# sensor_board.net
KiCad netlist of a schematic drawn in Altium Designer
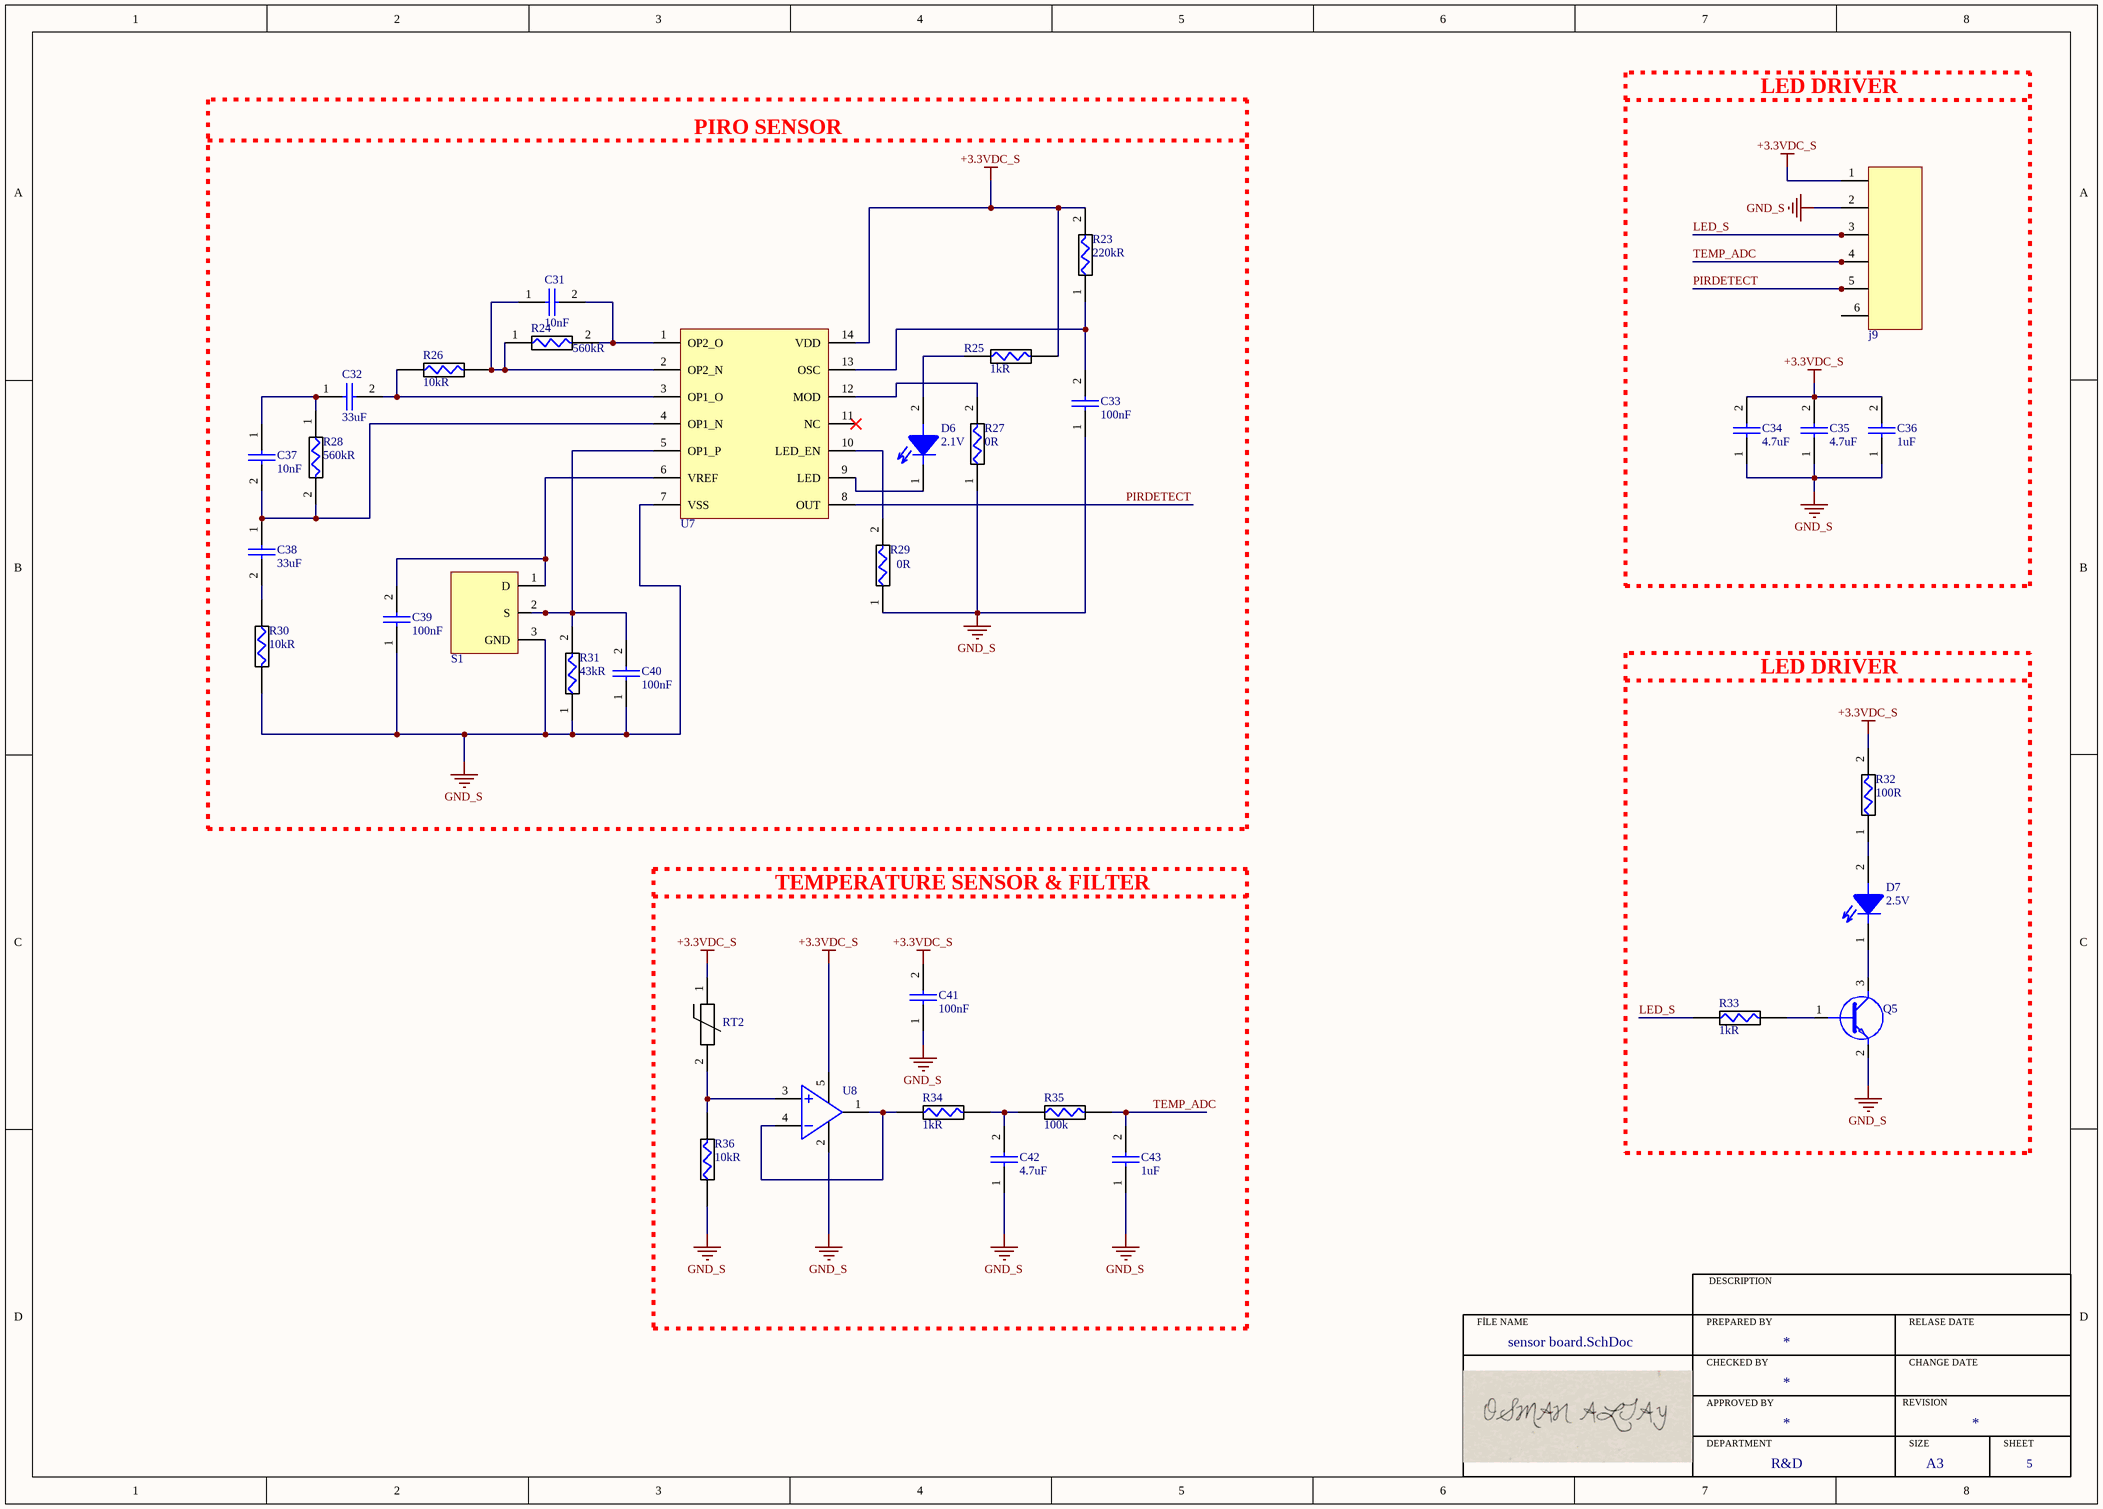
[diagram p0: sensor board.SchDoc]

(export (version "E")
  (design (tool "Eeschema 10.0.6"))
  (components
    (comp (ref "C31")
      (value "10nF")
      (footprint "CAP_0603")
      (description "CAP CER 10nF %10 0603")
      (fields
        (field (name "MANUFACTURER") "Walsin Technologies")
        (field (name "MANUFACTURER PART NUMBER") "0603B103K160CT")
        (field (name "DESIGNED BY") "Osman")
      )
      (libsource (lib "udemy_library") (part "CAP CER 10nF 0603"))
    )
    (comp (ref "C32")
      (value "33uF")
      (footprint "CAP_1206")
      (description "Multilayer Ceramic Capacitor, 33 uF, 25 V, ± 20%, X5R, 1206 [3216 Metric]")
      (fields
        (field (name "MANUFACTURER") "TDK")
        (field (name "MANUFACTURER PART NUMBER") "C3216X5R1E336M160AC")
      )
      (libsource (lib "udemy_library") (part "CAP CER 33uF 0603"))
    )
    (comp (ref "C33")
      (value "100nF")
      (footprint "CAP_0603")
      (description "Capacitor, 0.1UF, 100V, MLCC, 0603;")
      (fields
        (field (name "MANUFACTURER") "KEMET")
        (field (name "MANUFACTURER PART NUMBER") "C0603C104K1RACTU")
        (field (name "DESIGNED BY") "Osman")
      )
      (libsource (lib "udemy_library") (part "CAP CER 100nf 0603"))
    )
    (comp (ref "C34")
      (value "4.7uF")
      (footprint "CAP_0805")
      (description "CAP CER 4.7uF %10 0805")
      (fields
        (field (name "MANUFACTURER") "Samsung")
        (field (name "MANUFACTURER PART NUMBER") "CL21A475KAQNNNE")
      )
      (libsource (lib "udemy_library") (part "CAP CER 4.7uF 0805"))
    )
    (comp (ref "C35")
      (value "4.7uF")
      (footprint "CAP_0805")
      (description "CAP CER 4.7uF %10 0805")
      (fields
        (field (name "MANUFACTURER") "Samsung")
        (field (name "MANUFACTURER PART NUMBER") "CL21A475KAQNNNE")
      )
      (libsource (lib "udemy_library") (part "CAP CER 4.7uF 0805"))
    )
    (comp (ref "C36")
      (value "1uF")
      (footprint "CAP_0805")
      (description "CAP CER 1uF %10 0805")
      (fields
        (field (name "MANUFACTURER") "Samsung")
        (field (name "MANUFACTURER PART NUMBER") "CL21B105KBFNNNE")
        (field (name "DESIGNED BY") "Osman")
      )
      (libsource (lib "udemy_library") (part "CAP CER 1uF 0805"))
    )
    (comp (ref "C37")
      (value "10nF")
      (footprint "CAP_0603")
      (description "CAP CER 10nF %10 0603")
      (fields
        (field (name "MANUFACTURER") "Walsin Technologies")
        (field (name "MANUFACTURER PART NUMBER") "0603B103K160CT")
        (field (name "DESIGNED BY") "Osman")
      )
      (libsource (lib "udemy_library") (part "CAP CER 10nF 0603"))
    )
    (comp (ref "C38")
      (value "33uF")
      (footprint "CAP_1206")
      (description "Multilayer Ceramic Capacitor, 33 uF, 25 V, ± 20%, X5R, 1206 [3216 Metric]")
      (fields
        (field (name "MANUFACTURER") "TDK")
        (field (name "MANUFACTURER PART NUMBER") "C3216X5R1E336M160AC")
      )
      (libsource (lib "udemy_library") (part "CAP CER 33uF 0603"))
    )
    (comp (ref "C39")
      (value "100nF")
      (footprint "CAP_0603")
      (description "Capacitor, 0.1UF, 100V, MLCC, 0603;")
      (fields
        (field (name "MANUFACTURER") "KEMET")
        (field (name "MANUFACTURER PART NUMBER") "C0603C104K1RACTU")
        (field (name "DESIGNED BY") "Osman")
      )
      (libsource (lib "udemy_library") (part "CAP CER 100nf 0603"))
    )
    (comp (ref "C40")
      (value "100nF")
      (footprint "CAP_0603")
      (description "Capacitor, 0.1UF, 100V, MLCC, 0603;")
      (fields
        (field (name "MANUFACTURER") "KEMET")
        (field (name "MANUFACTURER PART NUMBER") "C0603C104K1RACTU")
        (field (name "DESIGNED BY") "Osman")
      )
      (libsource (lib "udemy_library") (part "CAP CER 100nf 0603"))
    )
    (comp (ref "C41")
      (value "100nF")
      (footprint "CAP_0805")
      (description "CL21B104KBCNNNC")
      (fields
        (field (name "MANUFACTURER") "Samsung")
        (field (name "TOLERANCE") "10%")
        (field (name "DESIGNED BY") "OSMAN")
      )
      (libsource (lib "udemy_library") (part "CAP CER 100nF 0805"))
    )
    (comp (ref "C42")
      (value "4.7uF")
      (footprint "CAP_0805")
      (description "CAP CER 4.7uF %10 0805")
      (fields
        (field (name "MANUFACTURER") "Samsung")
        (field (name "MANUFACTURER PART NUMBER") "CL21A475KAQNNNE")
      )
      (libsource (lib "udemy_library") (part "CAP CER 4.7uF 0805"))
    )
    (comp (ref "C43")
      (value "1uF")
      (footprint "CAP_0805")
      (description "CAP CER 1uF %10 0805")
      (fields
        (field (name "MANUFACTURER") "Samsung")
        (field (name "MANUFACTURER PART NUMBER") "CL21B105KBFNNNE")
        (field (name "DESIGNED BY") "Osman")
      )
      (libsource (lib "udemy_library") (part "CAP CER 1uF 0805"))
    )
    (comp (ref "D6")
      (value "CMD17-21VGD/TR8")
      (footprint "LED_GREEN_0805")
      (description "CML CMD17-21VGD/TR8 LED SMT 0805 2.1V 7mcd 140deg Green 3K Part of the VCC Family of Products")
      (fields (field (name "MANUFACTURER") "VCC CHML") (field (name "FOWARD VOLTAGE") "2.1V"))
      (libsource (lib "udemy_library") (part "LED GREEN 0805"))
    )
    (comp (ref "D7")
      (value "LS R976-NR-1")
      (footprint "LED_RED_0805")
      (description "LED Uni-Color Super Red 645nm 2-Pin Chip 0805(2012Metric) T/R")
      (fields
        (field (name "MANUFACTURER") "Osram Opto")
        (field (name "MANUFACTURER PART NUMBER") "LSR976-NR-1")
        (field (name "FORWARD VOLTAGE") "2.5V")
        (field (name "DESIGNED BY") "Osman")
      )
      (libsource (lib "udemy_library") (part "LED RED 0805"))
    )
    (comp (ref "j9")
      (value "64800611622")
      (footprint "64800611622_")
      (description "WR-WTB Wire-to-Board Connectors 1.50 mm")
      (fields (field (name "MANUFACTURER") "Wurth Electronics"))
      (libsource (lib "udemy_library") (part "64800611622_conn_6pin"))
    )
    (comp (ref "Q5")
      (value "MMBT3904-7-F")
      (footprint "SOT23-3")
      (description "Transistor General Purpose BJT NPN 40 Volt 0.2A Automotive 3-Pin SOT-23")
      (fields (field (name "MANUFACTURER") "Diodes Zetex") (field (name "DESIGNED BY") "Osman"))
      (libsource (lib "udemy_library") (part "MMBT3904-7-F"))
    )
    (comp (ref "R23")
      (value "220kR")
      (footprint "RES_0603")
      (description "SMD Chip Resistor, 220 kOhm, ± 5%, 50 mW, 0201 [0603 Metric], Thick Film, General Purpose")
      (fields
        (field (name "MANUFACTURER") "Yageo")
        (field (name "MANUFACTURER PART NUMBER") "RC0201JR-07220KL")
      )
      (libsource (lib "udemy_library") (part "RES 220K OHM 0603"))
    )
    (comp (ref "R24")
      (value "560kR")
      (footprint "RES_0603")
      (description "SMD Chip Resistor, 560 kOhm, ± 5%, 100 mW, 0603 [1608 Metric], Thick Film, General Purpose")
      (fields
        (field (name "MANUFACTURER") "Yageo")
        (field (name "MANUFACTURER PART NUMBER") "RC0603JR-07560KL")
        (field (name "DESIGNED BY") "OSMAN")
      )
      (libsource (lib "") (part "RES 560K OHM 0603_1"))
    )
    (comp (ref "R25")
      (value "1kR")
      (footprint "RES_0603")
      (description "Res Thick Film 0201 1K Ohm 5% 0.05W(1/20W) ±200ppm/C Pad SMD T/R")
      (fields
        (field (name "MANUFACTURER") "Yageo")
        (field (name "MANUFACTURER PART NUMBER") "RC0201JR-071KL")
      )
      (libsource (lib "udemy_library") (part "RES 1K OHM 0603"))
    )
    (comp (ref "R26")
      (value "10kR")
      (footprint "RES_0603")
      (description "RES 10K OHM %10 0603")
      (fields
        (field (name "MANUFACTURER") "Yageo")
        (field (name "MANUFACTURER PART NUMBER") "RC0603FR-0710KL")
        (field (name "DESIGNED NY") "Osman")
      )
      (libsource (lib "udemy_library") (part "RES 10K Ohm 0603"))
    )
    (comp (ref "R27")
      (value "0R")
      (footprint "RES_0603")
      (description "Zero Ohm Resistor, Jumper, 0603 [1608 Metric], Thick Film, 100 mW, 1 A, Surface Mount")
      (fields
        (field (name "MANUFACTURER") "Yageo")
        (field (name "MANUFACTURER PART NUMBER") "RC0603JR-070RL")
        (field (name "DESIGNED BY") "Osman")
      )
      (libsource (lib "udemy_library") (part "RES 0 OHM 603"))
    )
    (comp (ref "R28")
      (value "560kR")
      (footprint "RES_0603")
      (description "SMD Chip Resistor, 560 kOhm, ± 5%, 100 mW, 0603 [1608 Metric], Thick Film, General Purpose")
      (fields
        (field (name "MANUFACTURER") "Yageo")
        (field (name "MANUFACTURER PART NUMBER") "RC0603JR-07560KL")
        (field (name "DESIGNED BY") "OSMAN")
      )
      (libsource (lib "udemy_library") (part "RES 560K OHM 0603"))
    )
    (comp (ref "R29")
      (value "0R")
      (footprint "RES_0603")
      (description "Zero Ohm Resistor, Jumper, 0603 [1608 Metric], Thick Film, 100 mW, 1 A, Surface Mount")
      (fields
        (field (name "MANUFACTURER") "Yageo")
        (field (name "MANUFACTURER PART NUMBER") "RC0603JR-070RL")
        (field (name "DESIGNED BY") "Osman")
      )
      (libsource (lib "udemy_library") (part "RES 0 OHM 603"))
    )
    (comp (ref "R30")
      (value "10kR")
      (footprint "RES_0603")
      (description "RES 10K OHM %10 0603")
      (fields
        (field (name "MANUFACTURER") "Yageo")
        (field (name "MANUFACTURER PART NUMBER") "RC0603FR-0710KL")
        (field (name "DESIGNED NY") "Osman")
      )
      (libsource (lib "") (part "RES 10K Ohm 0603_2"))
    )
    (comp (ref "R31")
      (value "43kR")
      (footprint "RES_0603")
      (description "Res Thick Film 0201 43K Ohm 5% 0.05W(1/20W) ±200ppm/C Pad SMD T/R")
      (fields
        (field (name "MANUFACTURER") "Yageo")
        (field (name "MANUFACTURER PART NUMBER") "RC0201JR-0743KL")
      )
      (libsource (lib "udemy_library") (part "RES 43K OHM 0603"))
    )
    (comp (ref "R32")
      (value "100R")
      (footprint "RES_0603")
      (description "SMD Chip Resistor, 100 Ohm, ± 1%, 100 mW, 0603 [1608 Metric], Thick Film, General Purpose")
      (fields
        (field (name "MANUFACTURER") "Yageo")
        (field (name "MANUFACTURER PART NUMBER") "RC0603FR-07100RL")
      )
      (libsource (lib "udemy_library") (part "RES 100 OHM 0603"))
    )
    (comp (ref "R33")
      (value "1kR")
      (footprint "RES_0603")
      (description "Res Thick Film 0201 1K Ohm 5% 0.05W(1/20W) ±200ppm/C Pad SMD T/R")
      (fields
        (field (name "MANUFACTURER") "Yageo")
        (field (name "MANUFACTURER PART NUMBER") "RC0201JR-071KL")
      )
      (libsource (lib "udemy_library") (part "RES 1K OHM 0603"))
    )
    (comp (ref "R34")
      (value "1kR")
      (footprint "RES_0603")
      (description "Res Thick Film 0201 1K Ohm 5% 0.05W(1/20W) ±200ppm/C Pad SMD T/R")
      (fields
        (field (name "MANUFACTURER") "Yageo")
        (field (name "MANUFACTURER PART NUMBER") "RC0201JR-071KL")
      )
      (libsource (lib "udemy_library") (part "RES 1K OHM 0603"))
    )
    (comp (ref "R35")
      (value "100k")
      (footprint "RES_0603")
      (description "Res Thick Film 0603 100K Ohm 1% 0.25W(1/4W) ±100ppm/°C Pad SMD T/R Automotive AEC-Q200")
      (fields
        (field (name "MANUFACTURER") "Yageo")
        (field (name "MANUFACTURER PART NUMBER") "SR0603FR-7T100KL")
      )
      (libsource (lib "udemy_library") (part "RES 100K OHM 0603"))
    )
    (comp (ref "R36")
      (value "10kR")
      (footprint "RES_0603")
      (description "RES 10K OHM %10 0603")
      (fields
        (field (name "MANUFACTURER") "Yageo")
        (field (name "MANUFACTURER PART NUMBER") "RC0603FR-0710KL")
        (field (name "DESIGNED NY") "Osman")
      )
      (libsource (lib "") (part "RES 10K Ohm 0603_1"))
    )
    (comp (ref "RT2")
      (value "TFPT1206L1002FM")
      (footprint "TFPT1206")
      (description "Thermistor PTC 10K Ohm 1% 2-Pin 1206 Surface Mount Solder Pad T/R Automotive")
      (fields
        (field (name "MANUFACTURER") "Vishay Dale")
        (field (name "TOLERANCE") "1%")
        (field (name "DESIGNED BY") "Osman")
      )
      (libsource (lib "udemy_library") (part "TFPT1206L1002FM"))
    )
    (comp (ref "S1")
      (value "LHI 878/3902")
      (footprint "LHI 878")
      (description "SENSOR PYRO DETECTOR DUAL MOTION")
      (libsource (lib "udemy_library") (part "LHI 878/3902"))
    )
    (comp (ref "U7")
      (value "NCS36000DRG")
      (footprint "SOIC-14")
      (description "NCS36000 Series Single 5.75V Passive Infrared Detector Controller (PIR) -SOIC-14")
      (fields (field (name "MANUFACTURER") "ON Semiconductor") (field (name "DESIGNED BY") "Osman"))
      (libsource (lib "udemy_library") (part "NCS36000DRG"))
    )
    (comp (ref "U8")
      (value "OPA314AIDBVR")
      (footprint "SOT23-5")
      (description "IC OPAMP GP 3MHZ RRO SOT23-5")
      (fields (field (name "MANUFACTURER") "Texas Instruments") (field (name "DESIGNED BY") "Osman"))
      (libsource (lib "udemy_library") (part "OPA314"))
    )
  )
  (nets
    (net (code "1") (name "+3.3VDC_S") (class "Default")
      (node (ref "C34") (pin "2") (pinfunction "2_2") (pintype "passive"))
      (node (ref "C35") (pin "2") (pinfunction "2_2") (pintype "passive"))
      (node (ref "C36") (pin "2") (pinfunction "2_2") (pintype "passive"))
      (node (ref "C41") (pin "2") (pinfunction "2_2") (pintype "passive"))
      (node (ref "R23") (pin "2") (pinfunction "2_2") (pintype "passive"))
      (node (ref "R25") (pin "2") (pinfunction "2_2") (pintype "passive"))
      (node (ref "R32") (pin "2") (pinfunction "2_2") (pintype "passive"))
      (node (ref "RT2") (pin "1") (pinfunction "1_1") (pintype "passive"))
      (node (ref "U7") (pin "14") (pinfunction "VDD_14") (pintype "passive"))
      (node (ref "U8") (pin "5") (pinfunction "V+_5") (pintype "passive"))
      (node (ref "j9") (pin "1") (pinfunction "1_1") (pintype "passive"))
    )
    (net (code "2") (name "/LED_S") (class "Default")
      (node (ref "R33") (pin "1") (pinfunction "1_1") (pintype "passive"))
      (node (ref "j9") (pin "3") (pinfunction "3_3") (pintype "passive"))
    )
    (net (code "3") (name "/PIRDETECT") (class "Default")
      (node (ref "U7") (pin "8") (pinfunction "OUT_8") (pintype "passive"))
      (node (ref "j9") (pin "5") (pinfunction "5_5") (pintype "passive"))
    )
    (net (code "4") (name "/TEMP_ADC") (class "Default")
      (node (ref "C43") (pin "2") (pinfunction "2_2") (pintype "passive"))
      (node (ref "R35") (pin "2") (pinfunction "2_2") (pintype "passive"))
      (node (ref "j9") (pin "4") (pinfunction "4_4") (pintype "passive"))
    )
    (net (code "5") (name "GND_S") (class "Default")
      (node (ref "C33") (pin "1") (pinfunction "1_1") (pintype "passive"))
      (node (ref "C34") (pin "1") (pinfunction "1_1") (pintype "passive"))
      (node (ref "C35") (pin "1") (pinfunction "1_1") (pintype "passive"))
      (node (ref "C36") (pin "1") (pinfunction "1_1") (pintype "passive"))
      (node (ref "C39") (pin "1") (pinfunction "1_1") (pintype "passive"))
      (node (ref "C40") (pin "1") (pinfunction "1_1") (pintype "passive"))
      (node (ref "C41") (pin "1") (pinfunction "1_1") (pintype "passive"))
      (node (ref "C42") (pin "1") (pinfunction "1_1") (pintype "passive"))
      (node (ref "C43") (pin "1") (pinfunction "1_1") (pintype "passive"))
      (node (ref "Q5") (pin "2") (pinfunction "E_2") (pintype "passive"))
      (node (ref "R27") (pin "1") (pinfunction "1_1") (pintype "passive"))
      (node (ref "R29") (pin "1") (pinfunction "1_1") (pintype "passive"))
      (node (ref "R30") (pin "2") (pinfunction "2_2") (pintype "passive"))
      (node (ref "R31") (pin "1") (pinfunction "1_1") (pintype "passive"))
      (node (ref "R36") (pin "1") (pinfunction "1_1") (pintype "passive"))
      (node (ref "S1") (pin "3") (pinfunction "GND_3") (pintype "passive"))
      (node (ref "U7") (pin "7") (pinfunction "VSS_7") (pintype "passive"))
      (node (ref "U8") (pin "2") (pinfunction "V-_2") (pintype "passive"))
      (node (ref "j9") (pin "2") (pinfunction "2_2") (pintype "passive"))
    )
    (net (code "6") (name "Net-(C32-Pad1)") (class "Default")
      (node (ref "C32") (pin "1") (pinfunction "1_1") (pintype "passive"))
      (node (ref "C37") (pin "1") (pinfunction "1_1") (pintype "passive"))
      (node (ref "R28") (pin "1") (pinfunction "1_1") (pintype "passive"))
    )
    (net (code "7") (name "Net-(C38-Pad2)") (class "Default")
      (node (ref "C38") (pin "2") (pinfunction "2_2") (pintype "passive"))
      (node (ref "R30") (pin "1") (pinfunction "1_1") (pintype "passive"))
    )
    (net (code "8") (name "Net-(C42-Pad2)") (class "Default")
      (node (ref "C42") (pin "2") (pinfunction "2_2") (pintype "passive"))
      (node (ref "R34") (pin "2") (pinfunction "2_2") (pintype "passive"))
      (node (ref "R35") (pin "1") (pinfunction "1_1") (pintype "passive"))
    )
    (net (code "9") (name "Net-(D6-Pad2)") (class "Default")
      (node (ref "D6") (pin "2") (pinfunction "2_2") (pintype "passive"))
      (node (ref "R25") (pin "1") (pinfunction "1_1") (pintype "passive"))
    )
    (net (code "10") (name "Net-(D7-Pad2)") (class "Default")
      (node (ref "D7") (pin "2") (pinfunction "2_2") (pintype "passive"))
      (node (ref "R32") (pin "1") (pinfunction "1_1") (pintype "passive"))
    )
    (net (code "11") (name "Net-(Q5-B)") (class "Default")
      (node (ref "Q5") (pin "1") (pinfunction "B_1") (pintype "passive"))
      (node (ref "R33") (pin "2") (pinfunction "2_2") (pintype "passive"))
    )
    (net (code "12") (name "Net-(Q5-C)") (class "Default")
      (node (ref "D7") (pin "1") (pinfunction "1_1") (pintype "passive"))
      (node (ref "Q5") (pin "3") (pinfunction "C_3") (pintype "passive"))
    )
    (net (code "13") (name "Net-(S1-D)") (class "Default")
      (node (ref "C39") (pin "2") (pinfunction "2_2") (pintype "passive"))
      (node (ref "S1") (pin "1") (pinfunction "D_1") (pintype "passive"))
      (node (ref "U7") (pin "6") (pinfunction "VREF_6") (pintype "passive"))
    )
    (net (code "14") (name "Net-(S1-S)") (class "Default")
      (node (ref "C40") (pin "2") (pinfunction "2_2") (pintype "passive"))
      (node (ref "R31") (pin "2") (pinfunction "2_2") (pintype "passive"))
      (node (ref "S1") (pin "2") (pinfunction "S_2") (pintype "passive"))
      (node (ref "U7") (pin "5") (pinfunction "OP1_P_5") (pintype "passive"))
    )
    (net (code "15") (name "Net-(U7-LED)") (class "Default")
      (node (ref "D6") (pin "1") (pinfunction "1_1") (pintype "passive"))
      (node (ref "U7") (pin "9") (pinfunction "LED_9") (pintype "passive"))
    )
    (net (code "16") (name "Net-(U7-LED_EN)") (class "Default")
      (node (ref "R29") (pin "2") (pinfunction "2_2") (pintype "passive"))
      (node (ref "U7") (pin "10") (pinfunction "LED_EN_10") (pintype "passive"))
    )
    (net (code "17") (name "Net-(U7-MOD)") (class "Default")
      (node (ref "R27") (pin "2") (pinfunction "2_2") (pintype "passive"))
      (node (ref "U7") (pin "12") (pinfunction "MOD_12") (pintype "passive"))
    )
    (net (code "18") (name "Net-(U7-OP1_N)") (class "Default")
      (node (ref "C37") (pin "2") (pinfunction "2_2") (pintype "passive"))
      (node (ref "C38") (pin "1") (pinfunction "1_1") (pintype "passive"))
      (node (ref "R28") (pin "2") (pinfunction "2_2") (pintype "passive"))
      (node (ref "U7") (pin "4") (pinfunction "OP1_N_4") (pintype "passive"))
    )
    (net (code "19") (name "Net-(U7-OP1_O)") (class "Default")
      (node (ref "C32") (pin "2") (pinfunction "2_2") (pintype "passive"))
      (node (ref "R26") (pin "1") (pinfunction "1_1") (pintype "passive"))
      (node (ref "U7") (pin "3") (pinfunction "OP1_O_3") (pintype "passive"))
    )
    (net (code "20") (name "Net-(U7-OP2_N)") (class "Default")
      (node (ref "C31") (pin "1") (pinfunction "1_1") (pintype "passive"))
      (node (ref "R24") (pin "1") (pinfunction "1_1") (pintype "passive"))
      (node (ref "R26") (pin "2") (pinfunction "2_2") (pintype "passive"))
      (node (ref "U7") (pin "2") (pinfunction "OP2_N_2") (pintype "passive"))
    )
    (net (code "21") (name "Net-(U7-OP2_O)") (class "Default")
      (node (ref "C31") (pin "2") (pinfunction "2_2") (pintype "passive"))
      (node (ref "R24") (pin "2") (pinfunction "2_2") (pintype "passive"))
      (node (ref "U7") (pin "1") (pinfunction "OP2_O_1") (pintype "passive"))
    )
    (net (code "22") (name "Net-(U7-OSC)") (class "Default")
      (node (ref "C33") (pin "2") (pinfunction "2_2") (pintype "passive"))
      (node (ref "R23") (pin "1") (pinfunction "1_1") (pintype "passive"))
      (node (ref "U7") (pin "13") (pinfunction "OSC_13") (pintype "passive"))
    )
    (net (code "23") (name "Net-(U8-+IN)") (class "Default")
      (node (ref "R36") (pin "2") (pinfunction "2_2") (pintype "passive"))
      (node (ref "RT2") (pin "2") (pinfunction "2_2") (pintype "passive"))
      (node (ref "U8") (pin "3") (pinfunction "+IN_3") (pintype "passive"))
    )
    (net (code "24") (name "Net-(U8--IN)") (class "Default")
      (node (ref "R34") (pin "1") (pinfunction "1_1") (pintype "passive"))
      (node (ref "U8") (pin "1") (pinfunction "OUT_1") (pintype "passive"))
      (node (ref "U8") (pin "4") (pinfunction "-IN_4") (pintype "passive"))
    )
    (net (code "25") (name "unconnected-(U7-NC-Pad11)") (class "Default")
      (node (ref "U7") (pin "11") (pinfunction "NC_11") (pintype "passive+no_connect"))
    )
    (net (code "26") (name "unconnected-(j9-Pad6)") (class "Default")
      (node (ref "j9") (pin "6") (pinfunction "6_6") (pintype "passive"))
    )
  )
)
